# power_supply_board_basic.net
KiCad netlist of a schematic drawn in EAGLE
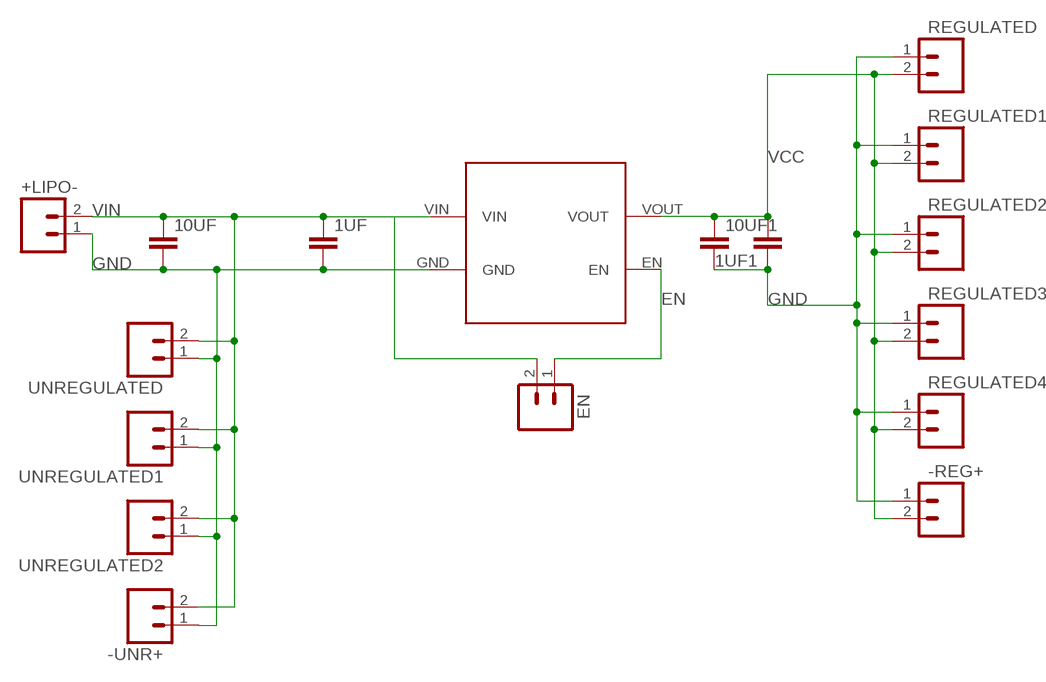
[diagram p0: schematic, sheet 1]

(export (version "E")
  (design (tool "Eeschema 10.0.6"))
  (components
    (comp (ref "+LIPO-")
      (value "M02PTH")
      (footprint "eagle-import:1X02")
      (libsource (lib "eagle-import") (part "M02PTH"))
    )
    (comp (ref "-REG+")
      (value "M02PTH")
      (footprint "eagle-import:1X02")
      (libsource (lib "eagle-import") (part "M02PTH"))
    )
    (comp (ref "-UNR+")
      (value "M02PTH")
      (footprint "eagle-import:1X02")
      (libsource (lib "eagle-import") (part "M02PTH"))
    )
    (comp (ref "1UF")
      (value "CAP0603-CAP")
      (footprint "eagle-import:0603-CAP")
      (libsource (lib "eagle-import") (part "CAP0603-CAP"))
    )
    (comp (ref "1UF1")
      (value "CAP0603-CAP")
      (footprint "eagle-import:0603-CAP")
      (libsource (lib "eagle-import") (part "CAP0603-CAP"))
    )
    (comp (ref "10UF")
      (value "CAP0603-CAP")
      (footprint "eagle-import:0603-CAP")
      (libsource (lib "eagle-import") (part "CAP0603-CAP"))
    )
    (comp (ref "10UF1")
      (value "CAP0603-CAP")
      (footprint "eagle-import:0603-CAP")
      (libsource (lib "eagle-import") (part "CAP0603-CAP"))
    )
    (comp (ref "EN")
      (value "M02PTH")
      (footprint "eagle-import:1X02")
      (libsource (lib "eagle-import") (part "M02PTH"))
    )
    (comp (ref "REGULATED")
      (value "M02PTH")
      (footprint "eagle-import:1X02")
      (libsource (lib "eagle-import") (part "M02PTH"))
    )
    (comp (ref "REGULATED1")
      (value "M02PTH")
      (footprint "eagle-import:1X02")
      (libsource (lib "eagle-import") (part "M02PTH"))
    )
    (comp (ref "REGULATED2")
      (value "M02PTH")
      (footprint "eagle-import:1X02")
      (libsource (lib "eagle-import") (part "M02PTH"))
    )
    (comp (ref "REGULATED3")
      (value "M02PTH")
      (footprint "eagle-import:1X02")
      (libsource (lib "eagle-import") (part "M02PTH"))
    )
    (comp (ref "REGULATED4")
      (value "M02PTH")
      (footprint "eagle-import:1X02")
      (libsource (lib "eagle-import") (part "M02PTH"))
    )
    (comp (ref "U$2")
      (value "AP2112K")
      (footprint "eagle-import:AP2112K-SOT23-5")
      (libsource (lib "eagle-import") (part "AP2112K"))
    )
    (comp (ref "UNREGULATED")
      (value "M02PTH")
      (footprint "eagle-import:1X02")
      (libsource (lib "eagle-import") (part "M02PTH"))
    )
    (comp (ref "UNREGULATED1")
      (value "M02PTH")
      (footprint "eagle-import:1X02")
      (libsource (lib "eagle-import") (part "M02PTH"))
    )
    (comp (ref "UNREGULATED2")
      (value "M02PTH")
      (footprint "eagle-import:1X02")
      (libsource (lib "eagle-import") (part "M02PTH"))
    )
  )
  (nets
    (net (code "1") (name "/EN") (class "Default")
      (node (ref "EN") (pin "1") (pinfunction "1_1") (pintype "passive"))
      (node (ref "U$2") (pin "EN") (pinfunction "EN_EN") (pintype "bidirectional"))
    )
    (net (code "2") (name "/GND") (class "Default")
      (node (ref "+LIPO-") (pin "1") (pinfunction "1_1") (pintype "passive"))
      (node (ref "-REG+") (pin "1") (pinfunction "1_1") (pintype "passive"))
      (node (ref "-UNR+") (pin "1") (pinfunction "1_1") (pintype "passive"))
      (node (ref "10UF") (pin "2") (pinfunction "2_2") (pintype "passive"))
      (node (ref "10UF1") (pin "2") (pinfunction "2_2") (pintype "passive"))
      (node (ref "1UF") (pin "2") (pinfunction "2_2") (pintype "passive"))
      (node (ref "1UF1") (pin "1") (pinfunction "1_1") (pintype "passive"))
      (node (ref "REGULATED") (pin "1") (pinfunction "1_1") (pintype "passive"))
      (node (ref "REGULATED1") (pin "1") (pinfunction "1_1") (pintype "passive"))
      (node (ref "REGULATED2") (pin "1") (pinfunction "1_1") (pintype "passive"))
      (node (ref "REGULATED3") (pin "1") (pinfunction "1_1") (pintype "passive"))
      (node (ref "REGULATED4") (pin "1") (pinfunction "1_1") (pintype "passive"))
      (node (ref "U$2") (pin "GND") (pinfunction "GND_GND") (pintype "bidirectional"))
      (node (ref "UNREGULATED") (pin "1") (pinfunction "1_1") (pintype "passive"))
      (node (ref "UNREGULATED1") (pin "1") (pinfunction "1_1") (pintype "passive"))
      (node (ref "UNREGULATED2") (pin "1") (pinfunction "1_1") (pintype "passive"))
    )
    (net (code "3") (name "/VCC") (class "Default")
      (node (ref "-REG+") (pin "2") (pinfunction "2_2") (pintype "passive"))
      (node (ref "10UF1") (pin "1") (pinfunction "1_1") (pintype "passive"))
      (node (ref "1UF1") (pin "2") (pinfunction "2_2") (pintype "passive"))
      (node (ref "REGULATED") (pin "2") (pinfunction "2_2") (pintype "passive"))
      (node (ref "REGULATED1") (pin "2") (pinfunction "2_2") (pintype "passive"))
      (node (ref "REGULATED2") (pin "2") (pinfunction "2_2") (pintype "passive"))
      (node (ref "REGULATED3") (pin "2") (pinfunction "2_2") (pintype "passive"))
      (node (ref "REGULATED4") (pin "2") (pinfunction "2_2") (pintype "passive"))
      (node (ref "U$2") (pin "VOUT") (pinfunction "VOUT_VOUT") (pintype "bidirectional"))
    )
    (net (code "4") (name "/VIN") (class "Default")
      (node (ref "+LIPO-") (pin "2") (pinfunction "2_2") (pintype "passive"))
      (node (ref "-UNR+") (pin "2") (pinfunction "2_2") (pintype "passive"))
      (node (ref "10UF") (pin "1") (pinfunction "1_1") (pintype "passive"))
      (node (ref "1UF") (pin "1") (pinfunction "1_1") (pintype "passive"))
      (node (ref "EN") (pin "2") (pinfunction "2_2") (pintype "passive"))
      (node (ref "U$2") (pin "VIN") (pinfunction "VIN_VIN") (pintype "bidirectional"))
      (node (ref "UNREGULATED") (pin "2") (pinfunction "2_2") (pintype "passive"))
      (node (ref "UNREGULATED1") (pin "2") (pinfunction "2_2") (pintype "passive"))
      (node (ref "UNREGULATED2") (pin "2") (pinfunction "2_2") (pintype "passive"))
    )
  )
)
